# TeamFlag.net
KiCad netlist of a schematic drawn in EAGLE
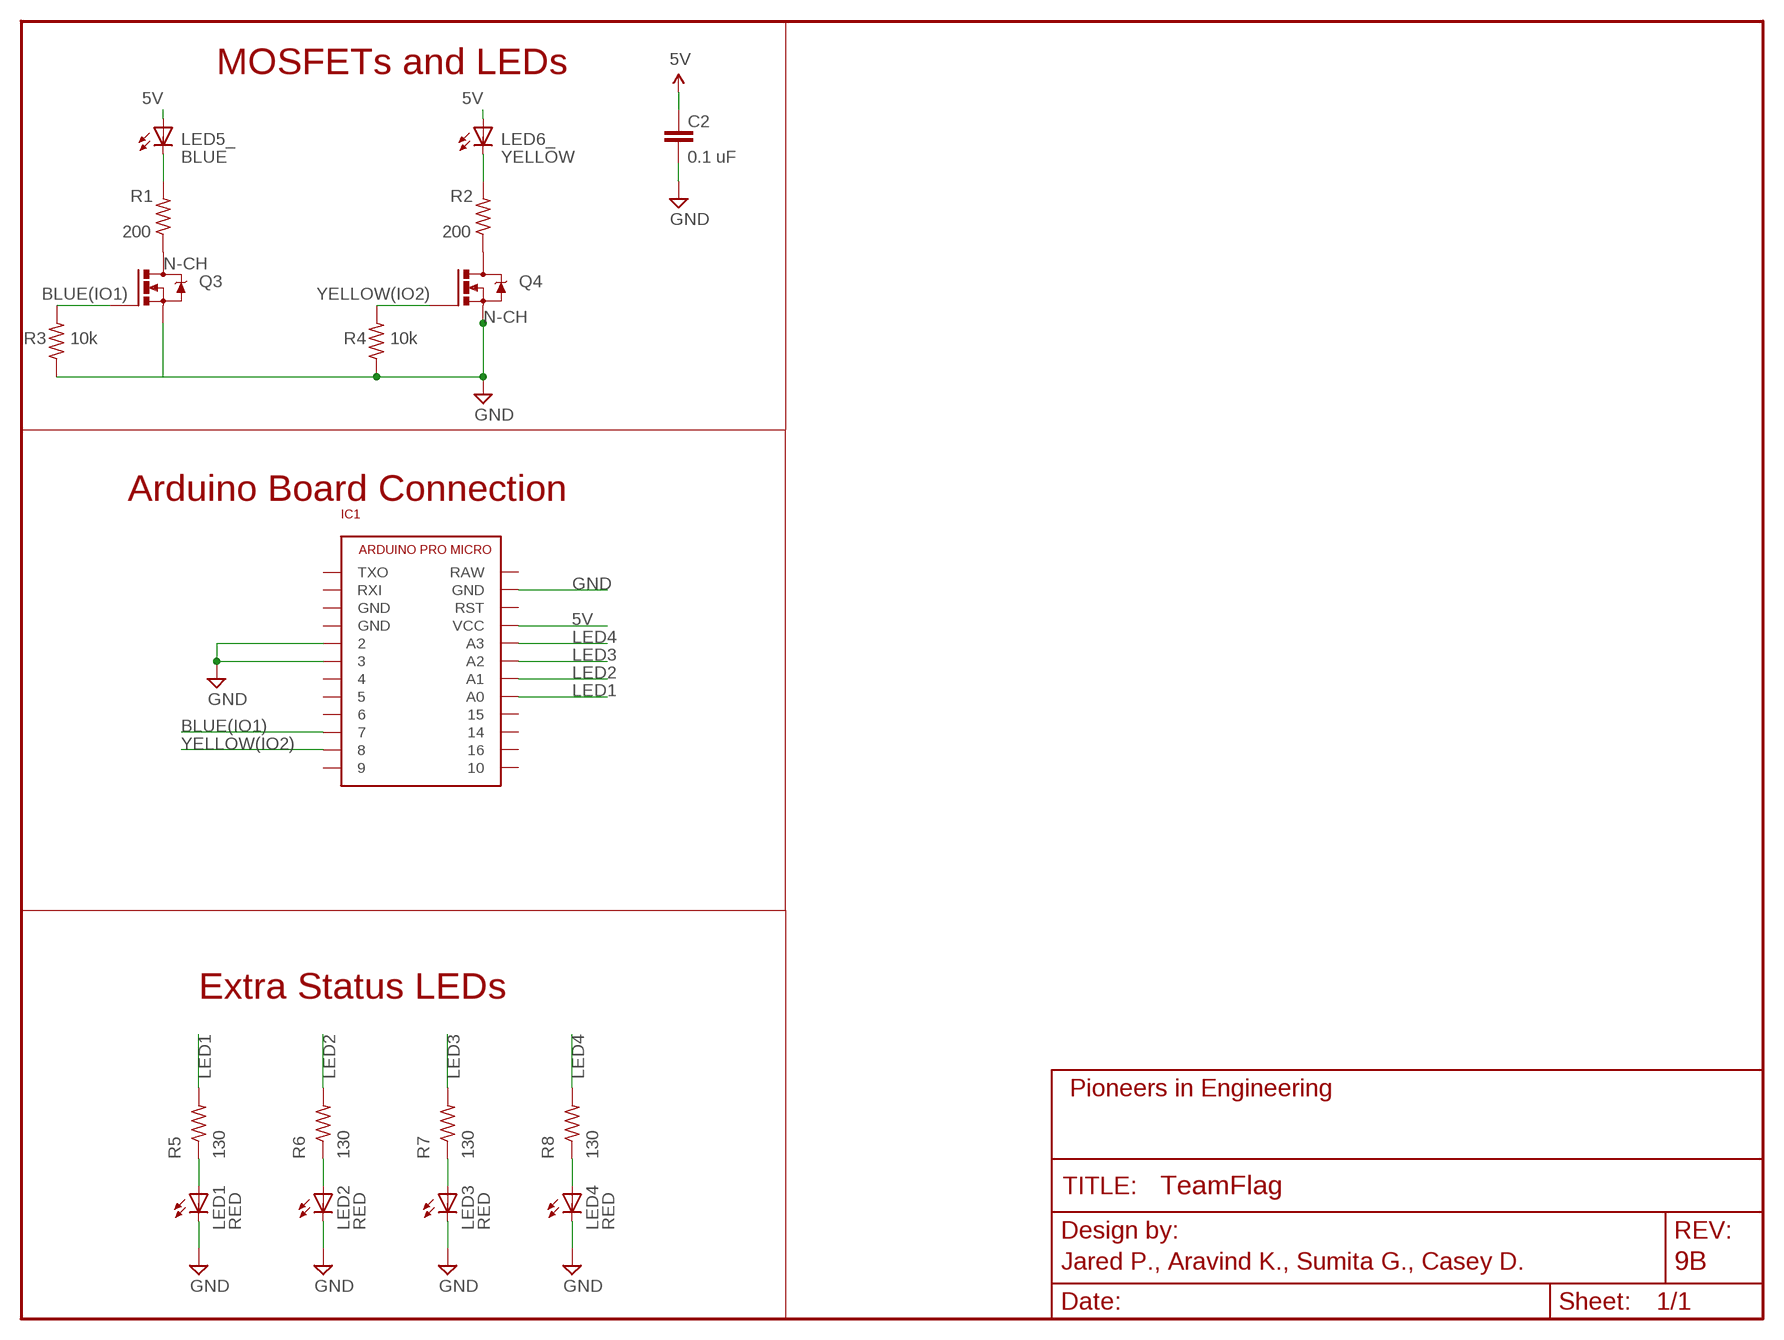
[diagram p0: schematic, sheet 1]

(export (version "E")
  (design (tool "Eeschema 10.0.6"))
  (components
    (comp (ref "C2")
      (value "0.1 uF")
      (footprint "eagle-import:0603-CAP")
      (libsource (lib "eagle-import") (part "CAP0603-CAP"))
    )
    (comp (ref "IC1")
      (value "ARDUINO_PRO_MICROSMD")
      (footprint "eagle-import:ARDUINO_PRO_MICRO_SM")
      (libsource (lib "eagle-import") (part "ARDUINO_PRO_MICROSMD"))
    )
    (comp (ref "LED1")
      (value "RED")
      (footprint "eagle-import:LED-0805")
      (libsource (lib "eagle-import") (part "LED0805"))
    )
    (comp (ref "LED2")
      (value "RED")
      (footprint "eagle-import:LED-0805")
      (libsource (lib "eagle-import") (part "LED0805"))
    )
    (comp (ref "LED3")
      (value "RED")
      (footprint "eagle-import:LED-0805")
      (libsource (lib "eagle-import") (part "LED0805"))
    )
    (comp (ref "LED4")
      (value "RED")
      (footprint "eagle-import:LED-0805")
      (libsource (lib "eagle-import") (part "LED0805"))
    )
    (comp (ref "LED5_")
      (value "BLUE")
      (footprint "eagle-import:LED5MM-NOFLAT")
      (libsource (lib "eagle-import") (part "LEDLED5MM-NOFLAT"))
    )
    (comp (ref "LED6_")
      (value "YELLOW")
      (footprint "eagle-import:LED5MM-NOFLAT")
      (libsource (lib "eagle-import") (part "LEDLED5MM-NOFLAT"))
    )
    (comp (ref "Q3")
      (value "N-CH")
      (footprint "eagle-import:SOT23-3")
      (libsource (lib "eagle-import") (part "N-CHANNEL-MOSFETSOT23-3"))
    )
    (comp (ref "Q4")
      (value "N-CH")
      (footprint "eagle-import:SOT23-3")
      (libsource (lib "eagle-import") (part "N-CHANNEL-MOSFETSOT23-3"))
    )
    (comp (ref "R1")
      (value "200")
      (footprint "eagle-import:R0603")
      (fields (field (name "MANUFACTURER") "Rohm Semiconductor"))
      (libsource (lib "eagle-import") (part "R-US_R0603"))
    )
    (comp (ref "R2")
      (value "200")
      (footprint "eagle-import:R0603")
      (fields (field (name "MANUFACTURER") "Rohm Semiconductor"))
      (libsource (lib "eagle-import") (part "R-US_R0603"))
    )
    (comp (ref "R3")
      (value "10k")
      (footprint "eagle-import:R0603")
      (fields (field (name "MANUFACTURER") "Rohm Semiconductor"))
      (libsource (lib "eagle-import") (part "R-US_R0603"))
    )
    (comp (ref "R4")
      (value "10k")
      (footprint "eagle-import:R0603")
      (fields (field (name "MANUFACTURER") "Rohm Semiconductor"))
      (libsource (lib "eagle-import") (part "R-US_R0603"))
    )
    (comp (ref "R5")
      (value "130")
      (footprint "eagle-import:R0603")
      (fields (field (name "MANUFACTURER") "Rohm Semiconductor"))
      (libsource (lib "eagle-import") (part "R-US_R0603"))
    )
    (comp (ref "R6")
      (value "130")
      (footprint "eagle-import:R0603")
      (fields (field (name "MANUFACTURER") "Rohm Semiconductor"))
      (libsource (lib "eagle-import") (part "R-US_R0603"))
    )
    (comp (ref "R7")
      (value "130")
      (footprint "eagle-import:R0603")
      (fields (field (name "MANUFACTURER") "Rohm Semiconductor"))
      (libsource (lib "eagle-import") (part "R-US_R0603"))
    )
    (comp (ref "R8")
      (value "130")
      (footprint "eagle-import:R0603")
      (fields (field (name "MANUFACTURER") "Rohm Semiconductor"))
      (libsource (lib "eagle-import") (part "R-US_R0603"))
    )
  )
  (nets
    (net (code "1") (name "/BLUE(IO1)") (class "Default")
      (node (ref "IC1") (pin "7") (pinfunction "7_7") (pintype "bidirectional"))
      (node (ref "Q3") (pin "1") (pinfunction "G_1") (pintype "passive"))
      (node (ref "R3") (pin "2") (pinfunction "2_2") (pintype "passive"))
    )
    (net (code "2") (name "/LED1") (class "Default")
      (node (ref "IC1") (pin "A0") (pinfunction "A0_A0") (pintype "bidirectional"))
      (node (ref "R5") (pin "2") (pinfunction "2_2") (pintype "passive"))
    )
    (net (code "3") (name "/LED2") (class "Default")
      (node (ref "IC1") (pin "A1") (pinfunction "A1_A1") (pintype "bidirectional"))
      (node (ref "R6") (pin "2") (pinfunction "2_2") (pintype "passive"))
    )
    (net (code "4") (name "/LED3") (class "Default")
      (node (ref "IC1") (pin "A2") (pinfunction "A2_A2") (pintype "bidirectional"))
      (node (ref "R7") (pin "2") (pinfunction "2_2") (pintype "passive"))
    )
    (net (code "5") (name "/LED4") (class "Default")
      (node (ref "IC1") (pin "A3") (pinfunction "A3_A3") (pintype "bidirectional"))
      (node (ref "R8") (pin "2") (pinfunction "2_2") (pintype "passive"))
    )
    (net (code "6") (name "/YELLOW(IO2)") (class "Default")
      (node (ref "IC1") (pin "8") (pinfunction "8_8") (pintype "bidirectional"))
      (node (ref "Q4") (pin "1") (pinfunction "G_1") (pintype "passive"))
      (node (ref "R4") (pin "2") (pinfunction "2_2") (pintype "passive"))
    )
    (net (code "7") (name "5V") (class "Default")
      (node (ref "C2") (pin "1") (pinfunction "1_1") (pintype "passive"))
      (node (ref "IC1") (pin "VCC") (pinfunction "VCC_VCC") (pintype "bidirectional"))
      (node (ref "LED5_") (pin "A") (pinfunction "A_A") (pintype "passive"))
      (node (ref "LED6_") (pin "A") (pinfunction "A_A") (pintype "passive"))
    )
    (net (code "8") (name "GND") (class "Default")
      (node (ref "C2") (pin "2") (pinfunction "2_2") (pintype "passive"))
      (node (ref "IC1") (pin "2") (pinfunction "2_2") (pintype "bidirectional"))
      (node (ref "IC1") (pin "3") (pinfunction "3_3") (pintype "bidirectional"))
      (node (ref "IC1") (pin "GND@3") (pinfunction "GND_GND@3") (pintype "bidirectional"))
      (node (ref "LED1") (pin "C") (pinfunction "C_C") (pintype "passive"))
      (node (ref "LED2") (pin "C") (pinfunction "C_C") (pintype "passive"))
      (node (ref "LED3") (pin "C") (pinfunction "C_C") (pintype "passive"))
      (node (ref "LED4") (pin "C") (pinfunction "C_C") (pintype "passive"))
      (node (ref "Q3") (pin "2") (pinfunction "S_2") (pintype "passive"))
      (node (ref "Q4") (pin "2") (pinfunction "S_2") (pintype "passive"))
      (node (ref "R3") (pin "1") (pinfunction "1_1") (pintype "passive"))
      (node (ref "R4") (pin "1") (pinfunction "1_1") (pintype "passive"))
    )
    (net (code "9") (name "Net-(LED1-PadA)") (class "Default")
      (node (ref "LED1") (pin "A") (pinfunction "A_A") (pintype "passive"))
      (node (ref "R5") (pin "1") (pinfunction "1_1") (pintype "passive"))
    )
    (net (code "10") (name "Net-(LED2-PadA)") (class "Default")
      (node (ref "LED2") (pin "A") (pinfunction "A_A") (pintype "passive"))
      (node (ref "R6") (pin "1") (pinfunction "1_1") (pintype "passive"))
    )
    (net (code "11") (name "Net-(LED3-PadA)") (class "Default")
      (node (ref "LED3") (pin "A") (pinfunction "A_A") (pintype "passive"))
      (node (ref "R7") (pin "1") (pinfunction "1_1") (pintype "passive"))
    )
    (net (code "12") (name "Net-(LED4-PadA)") (class "Default")
      (node (ref "LED4") (pin "A") (pinfunction "A_A") (pintype "passive"))
      (node (ref "R8") (pin "1") (pinfunction "1_1") (pintype "passive"))
    )
    (net (code "13") (name "Net-(LED5_-C)") (class "Default")
      (node (ref "LED5_") (pin "K") (pinfunction "C_K") (pintype "passive"))
      (node (ref "R1") (pin "2") (pinfunction "2_2") (pintype "passive"))
    )
    (net (code "14") (name "Net-(LED6_-C)") (class "Default")
      (node (ref "LED6_") (pin "K") (pinfunction "C_K") (pintype "passive"))
      (node (ref "R2") (pin "2") (pinfunction "2_2") (pintype "passive"))
    )
    (net (code "15") (name "Net-(Q3-D)") (class "Default")
      (node (ref "Q3") (pin "3") (pinfunction "D_3") (pintype "passive"))
      (node (ref "R1") (pin "1") (pinfunction "1_1") (pintype "passive"))
    )
    (net (code "16") (name "Net-(Q4-D)") (class "Default")
      (node (ref "Q4") (pin "3") (pinfunction "D_3") (pintype "passive"))
      (node (ref "R2") (pin "1") (pinfunction "1_1") (pintype "passive"))
    )
    (net (code "17") (name "unconnected-(IC1-GND-PadGND@1)") (class "Default")
      (node (ref "IC1") (pin "GND@1") (pinfunction "GND_GND@1") (pintype "bidirectional"))
    )
    (net (code "18") (name "unconnected-(IC1-GND-PadGND@2)") (class "Default")
      (node (ref "IC1") (pin "GND@2") (pinfunction "GND_GND@2") (pintype "bidirectional"))
    )
    (net (code "19") (name "unconnected-(IC1-Pad4)") (class "Default")
      (node (ref "IC1") (pin "4") (pinfunction "4_4") (pintype "bidirectional"))
    )
    (net (code "20") (name "unconnected-(IC1-Pad5)") (class "Default")
      (node (ref "IC1") (pin "5") (pinfunction "5_5") (pintype "bidirectional"))
    )
    (net (code "21") (name "unconnected-(IC1-Pad6)") (class "Default")
      (node (ref "IC1") (pin "6") (pinfunction "6_6") (pintype "bidirectional"))
    )
    (net (code "22") (name "unconnected-(IC1-Pad9)") (class "Default")
      (node (ref "IC1") (pin "9") (pinfunction "9_9") (pintype "bidirectional"))
    )
    (net (code "23") (name "unconnected-(IC1-Pad10)") (class "Default")
      (node (ref "IC1") (pin "10") (pinfunction "10_10") (pintype "bidirectional"))
    )
    (net (code "24") (name "unconnected-(IC1-Pad14)") (class "Default")
      (node (ref "IC1") (pin "14") (pinfunction "14_14") (pintype "bidirectional"))
    )
    (net (code "25") (name "unconnected-(IC1-Pad15)") (class "Default")
      (node (ref "IC1") (pin "15") (pinfunction "15_15") (pintype "bidirectional"))
    )
    (net (code "26") (name "unconnected-(IC1-Pad16)") (class "Default")
      (node (ref "IC1") (pin "16") (pinfunction "16_16") (pintype "bidirectional"))
    )
    (net (code "27") (name "unconnected-(IC1-PadRAW)") (class "Default")
      (node (ref "IC1") (pin "RAW") (pinfunction "RAW_RAW") (pintype "bidirectional"))
    )
    (net (code "28") (name "unconnected-(IC1-PadRST)") (class "Default")
      (node (ref "IC1") (pin "RST") (pinfunction "RST_RST") (pintype "bidirectional"))
    )
    (net (code "29") (name "unconnected-(IC1-RXI-PadRX)") (class "Default")
      (node (ref "IC1") (pin "RX") (pinfunction "RXI_RX") (pintype "bidirectional"))
    )
    (net (code "30") (name "unconnected-(IC1-TXO-PadTX)") (class "Default")
      (node (ref "IC1") (pin "TX") (pinfunction "TXO_TX") (pintype "bidirectional"))
    )
  )
)
